# SCH_USB-C_PD_Decoy_Board_2023-05-30.net
KiCad netlist of a schematic drawn in EasyEDA
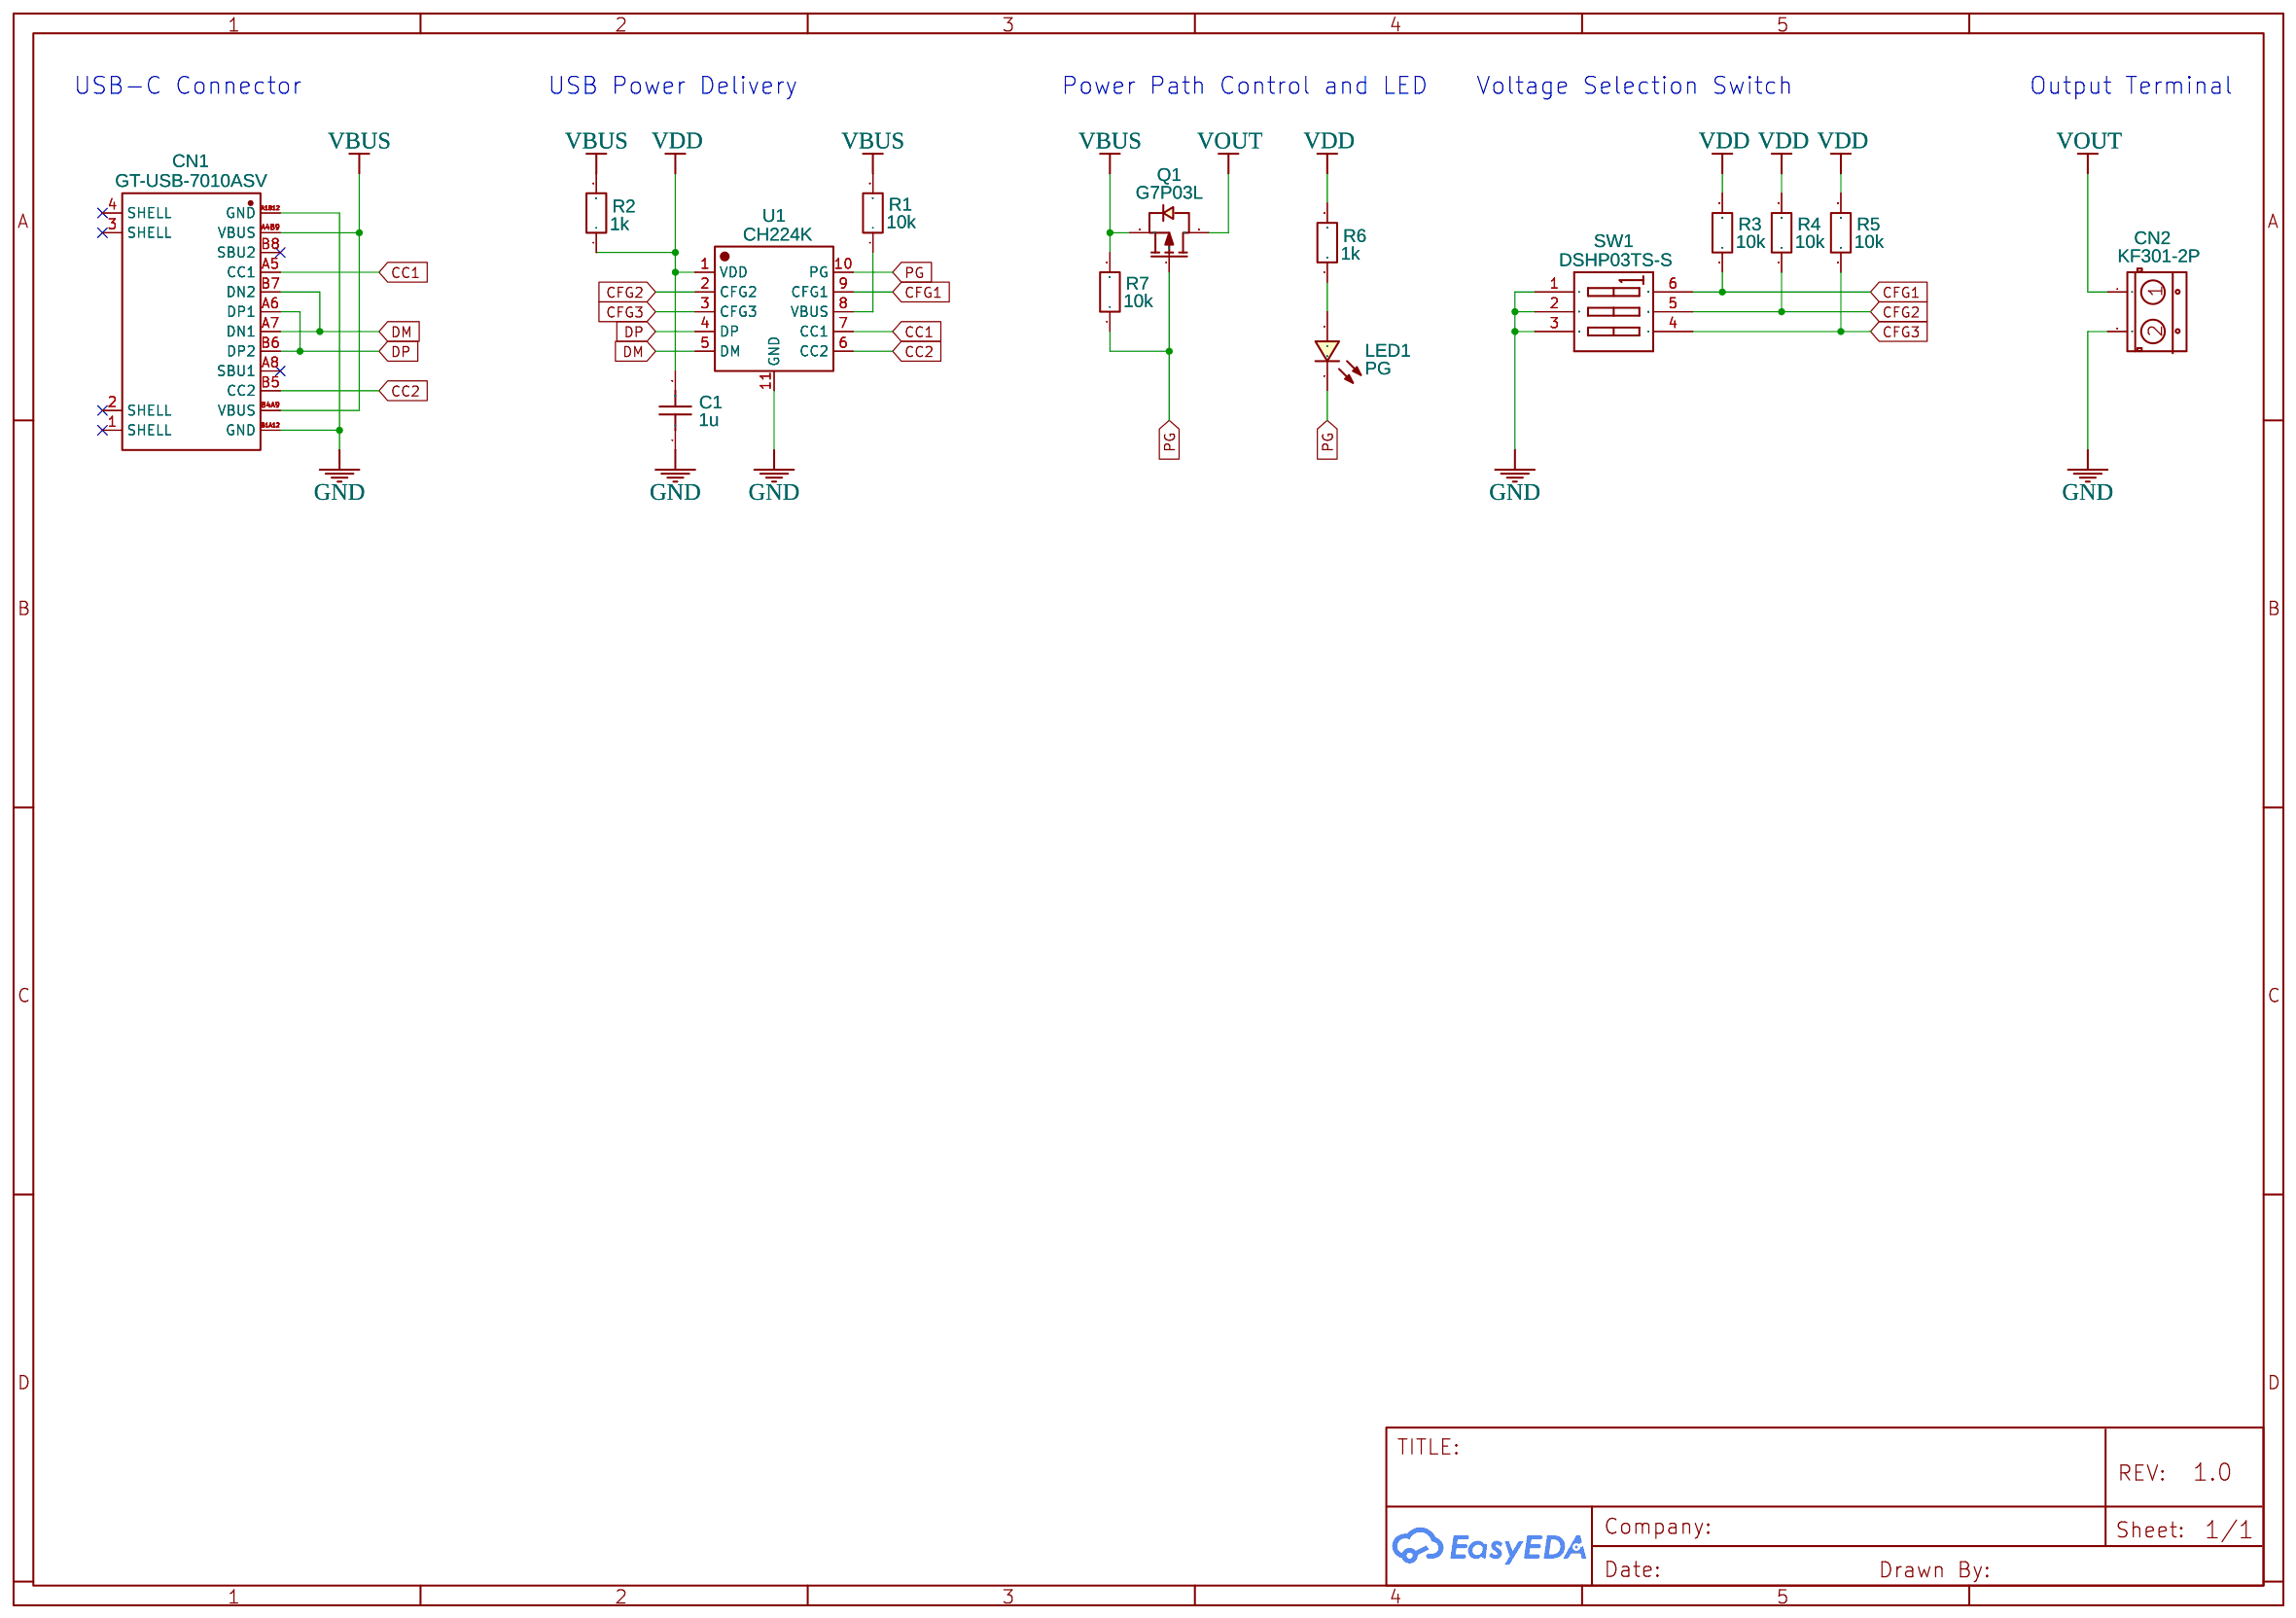
[diagram p0: schematic sheet]

(export (version "E")
  (design (tool "Eeschema 10.0.6"))
  (components
    (comp (ref "C1")
      (value "1u")
      (fields
        (field (name "BOM_Manufacturer Part") "CL10A105KB8NNNC")
        (field (name "BOM_Supplier Part") "C15849")
      )
      (libsource (lib "") (part "CC0603KRX7R9BB104"))
    )
    (comp (ref "CN1")
      (value "GT-USB-7010ASV")
      (fields (field (name "BOM_Supplier Part") "C2988369"))
      (libsource (lib "") (part "GT-USB-7010ASV"))
    )
    (comp (ref "CN2")
      (value "KF301-2P")
      (fields
        (field (name "BOM_Manufacturer Part") "KF301-5.0-2P")
        (field (name "BOM_Supplier Part") "C474881")
      )
      (libsource (lib "") (part "Unknown_1070_-680"))
    )
    (comp (ref "LED1")
      (value "PG")
      (fields
        (field (name "BOM_Manufacturer Part") "19-217/GHC-YR1S2/3T")
        (field (name "BOM_Supplier Part") "C72043")
      )
      (libsource (lib "") (part "LED-0603-GREEN"))
    )
    (comp (ref "Q1")
      (value "G7P03L")
      (fields (field (name "BOM_Supplier Part") "C840062"))
      (libsource (lib "") (part "G7P03L"))
    )
    (comp (ref "R1")
      (value "10k")
      (fields
        (field (name "BOM_Manufacturer Part") "0603WAF1002T5E")
        (field (name "BOM_Supplier Part") "C25804")
      )
      (libsource (lib "") (part "Res_0603(1/10W)_EU"))
    )
    (comp (ref "R2")
      (value "1k")
      (fields
        (field (name "BOM_Manufacturer Part") "0603WAF1001T5E")
        (field (name "BOM_Supplier Part") "C21190")
      )
      (libsource (lib "") (part "Res_0603(1/10W)_EU"))
    )
    (comp (ref "R3")
      (value "10k")
      (fields
        (field (name "BOM_Manufacturer Part") "0603WAF1002T5E")
        (field (name "BOM_Supplier Part") "C25804")
      )
      (libsource (lib "") (part "Res_0603(1/10W)_EU"))
    )
    (comp (ref "R4")
      (value "10k")
      (fields
        (field (name "BOM_Manufacturer Part") "0603WAF1002T5E")
        (field (name "BOM_Supplier Part") "C25804")
      )
      (libsource (lib "") (part "Res_0603(1/10W)_EU"))
    )
    (comp (ref "R5")
      (value "10k")
      (fields
        (field (name "BOM_Manufacturer Part") "0603WAF1002T5E")
        (field (name "BOM_Supplier Part") "C25804")
      )
      (libsource (lib "") (part "Res_0603(1/10W)_EU"))
    )
    (comp (ref "R6")
      (value "1k")
      (fields
        (field (name "BOM_Manufacturer Part") "0603WAF1001T5E")
        (field (name "BOM_Supplier Part") "C21190")
      )
      (libsource (lib "") (part "Res_0603(1/10W)_EU"))
    )
    (comp (ref "R7")
      (value "10k")
      (fields
        (field (name "BOM_Manufacturer Part") "0603WAF1002T5E")
        (field (name "BOM_Supplier Part") "C25804")
      )
      (libsource (lib "") (part "Res_0603(1/10W)_EU"))
    )
    (comp (ref "SW1")
      (value "DSHP03TS-S")
      (fields (field (name "BOM_Supplier Part") "C319051"))
      (libsource (lib "") (part "DSHP03TS-S"))
    )
    (comp (ref "U1") (value "CH224K") (libsource (lib "") (part "CH224K")))
  )
  (nets
    (net (code "1") (name "CC1") (class "Default")
      (node (ref "CN1") (pin "A5") (pinfunction "CC1_A5") (pintype "unspecified"))
      (node (ref "U1") (pin "7") (pinfunction "CC1_7") (pintype "unspecified"))
    )
    (net (code "2") (name "CC2") (class "Default")
      (node (ref "CN1") (pin "B5") (pinfunction "CC2_B5") (pintype "unspecified"))
      (node (ref "U1") (pin "6") (pinfunction "CC2_6") (pintype "unspecified"))
    )
    (net (code "3") (name "CFG1") (class "Default")
      (node (ref "R3") (pin "1") (pinfunction "1_1") (pintype "unspecified"))
      (node (ref "SW1") (pin "6") (pinfunction "6_6") (pintype "input"))
      (node (ref "U1") (pin "9") (pinfunction "CFG1_9") (pintype "unspecified"))
    )
    (net (code "4") (name "CFG2") (class "Default")
      (node (ref "R4") (pin "1") (pinfunction "1_1") (pintype "unspecified"))
      (node (ref "SW1") (pin "5") (pinfunction "5_5") (pintype "input"))
      (node (ref "U1") (pin "2") (pinfunction "CFG2_2") (pintype "unspecified"))
    )
    (net (code "5") (name "CFG3") (class "Default")
      (node (ref "R5") (pin "1") (pinfunction "1_1") (pintype "unspecified"))
      (node (ref "SW1") (pin "4") (pinfunction "4_4") (pintype "input"))
      (node (ref "U1") (pin "3") (pinfunction "CFG3_3") (pintype "unspecified"))
    )
    (net (code "6") (name "DM") (class "Default")
      (node (ref "CN1") (pin "A7") (pinfunction "DN1_A7") (pintype "unspecified"))
      (node (ref "CN1") (pin "B7") (pinfunction "DN2_B7") (pintype "unspecified"))
      (node (ref "U1") (pin "5") (pinfunction "DM_5") (pintype "unspecified"))
    )
    (net (code "7") (name "DP") (class "Default")
      (node (ref "CN1") (pin "A6") (pinfunction "DP1_A6") (pintype "unspecified"))
      (node (ref "CN1") (pin "B6") (pinfunction "DP2_B6") (pintype "unspecified"))
      (node (ref "U1") (pin "4") (pinfunction "DP_4") (pintype "unspecified"))
    )
    (net (code "8") (name "GND") (class "Default")
      (node (ref "C1") (pin "1") (pinfunction "1_1") (pintype "unspecified"))
      (node (ref "CN1") (pin "A1B12") (pinfunction "GND_A1B12") (pintype "unspecified"))
      (node (ref "CN1") (pin "B1A12") (pinfunction "GND_B1A12") (pintype "unspecified"))
      (node (ref "CN2") (pin "2") (pinfunction "2_2") (pintype "unspecified"))
      (node (ref "SW1") (pin "1") (pinfunction "1_1") (pintype "input"))
      (node (ref "SW1") (pin "2") (pinfunction "2_2") (pintype "input"))
      (node (ref "SW1") (pin "3") (pinfunction "3_3") (pintype "input"))
      (node (ref "U1") (pin "11") (pinfunction "GND_11") (pintype "unspecified"))
    )
    (net (code "9") (name "Net-(LED1-A)") (class "Default")
      (node (ref "LED1") (pin "1") (pinfunction "A_1") (pintype "input"))
      (node (ref "R6") (pin "1") (pinfunction "1_1") (pintype "unspecified"))
    )
    (net (code "10") (name "Net-(U1-VBUS)") (class "Default")
      (node (ref "R1") (pin "1") (pinfunction "1_1") (pintype "unspecified"))
      (node (ref "U1") (pin "8") (pinfunction "VBUS_8") (pintype "unspecified"))
    )
    (net (code "11") (name "PG") (class "Default")
      (node (ref "LED1") (pin "2") (pinfunction "C_2") (pintype "input"))
      (node (ref "Q1") (pin "1") (pinfunction "G_1") (pintype "unspecified"))
      (node (ref "R7") (pin "1") (pinfunction "1_1") (pintype "unspecified"))
      (node (ref "U1") (pin "10") (pinfunction "PG_10") (pintype "unspecified"))
    )
    (net (code "12") (name "VBUS") (class "Default")
      (node (ref "CN1") (pin "A4B9") (pinfunction "VBUS_A4B9") (pintype "unspecified"))
      (node (ref "CN1") (pin "B4A9") (pinfunction "VBUS_B4A9") (pintype "unspecified"))
      (node (ref "Q1") (pin "2") (pinfunction "S_2") (pintype "unspecified"))
      (node (ref "R1") (pin "2") (pinfunction "2_2") (pintype "unspecified"))
      (node (ref "R2") (pin "2") (pinfunction "2_2") (pintype "unspecified"))
      (node (ref "R7") (pin "2") (pinfunction "2_2") (pintype "unspecified"))
    )
    (net (code "13") (name "VDD") (class "Default")
      (node (ref "C1") (pin "2") (pinfunction "2_2") (pintype "unspecified"))
      (node (ref "R2") (pin "1") (pinfunction "1_1") (pintype "unspecified"))
      (node (ref "R3") (pin "2") (pinfunction "2_2") (pintype "unspecified"))
      (node (ref "R4") (pin "2") (pinfunction "2_2") (pintype "unspecified"))
      (node (ref "R5") (pin "2") (pinfunction "2_2") (pintype "unspecified"))
      (node (ref "R6") (pin "2") (pinfunction "2_2") (pintype "unspecified"))
      (node (ref "U1") (pin "1") (pinfunction "VDD_1") (pintype "unspecified"))
    )
    (net (code "14") (name "VOUT") (class "Default")
      (node (ref "CN2") (pin "1") (pinfunction "1_1") (pintype "unspecified"))
      (node (ref "Q1") (pin "3") (pinfunction "D_3") (pintype "unspecified"))
    )
    (net (code "15") (name "unconnected-(CN1-SBU1-PadA8)") (class "Default")
      (node (ref "CN1") (pin "A8") (pinfunction "SBU1_A8") (pintype "unspecified+no_connect"))
    )
    (net (code "16") (name "unconnected-(CN1-SBU2-PadB8)") (class "Default")
      (node (ref "CN1") (pin "B8") (pinfunction "SBU2_B8") (pintype "unspecified+no_connect"))
    )
    (net (code "17") (name "unconnected-(CN1-SHELL-Pad1)") (class "Default")
      (node (ref "CN1") (pin "1") (pinfunction "SHELL_1") (pintype "unspecified+no_connect"))
    )
    (net (code "18") (name "unconnected-(CN1-SHELL-Pad2)") (class "Default")
      (node (ref "CN1") (pin "2") (pinfunction "SHELL_2") (pintype "unspecified+no_connect"))
    )
    (net (code "19") (name "unconnected-(CN1-SHELL-Pad3)") (class "Default")
      (node (ref "CN1") (pin "3") (pinfunction "SHELL_3") (pintype "unspecified+no_connect"))
    )
    (net (code "20") (name "unconnected-(CN1-SHELL-Pad4)") (class "Default")
      (node (ref "CN1") (pin "4") (pinfunction "SHELL_4") (pintype "unspecified+no_connect"))
    )
  )
)
